# GSM.net
KiCad netlist of a schematic drawn in Altium Designer
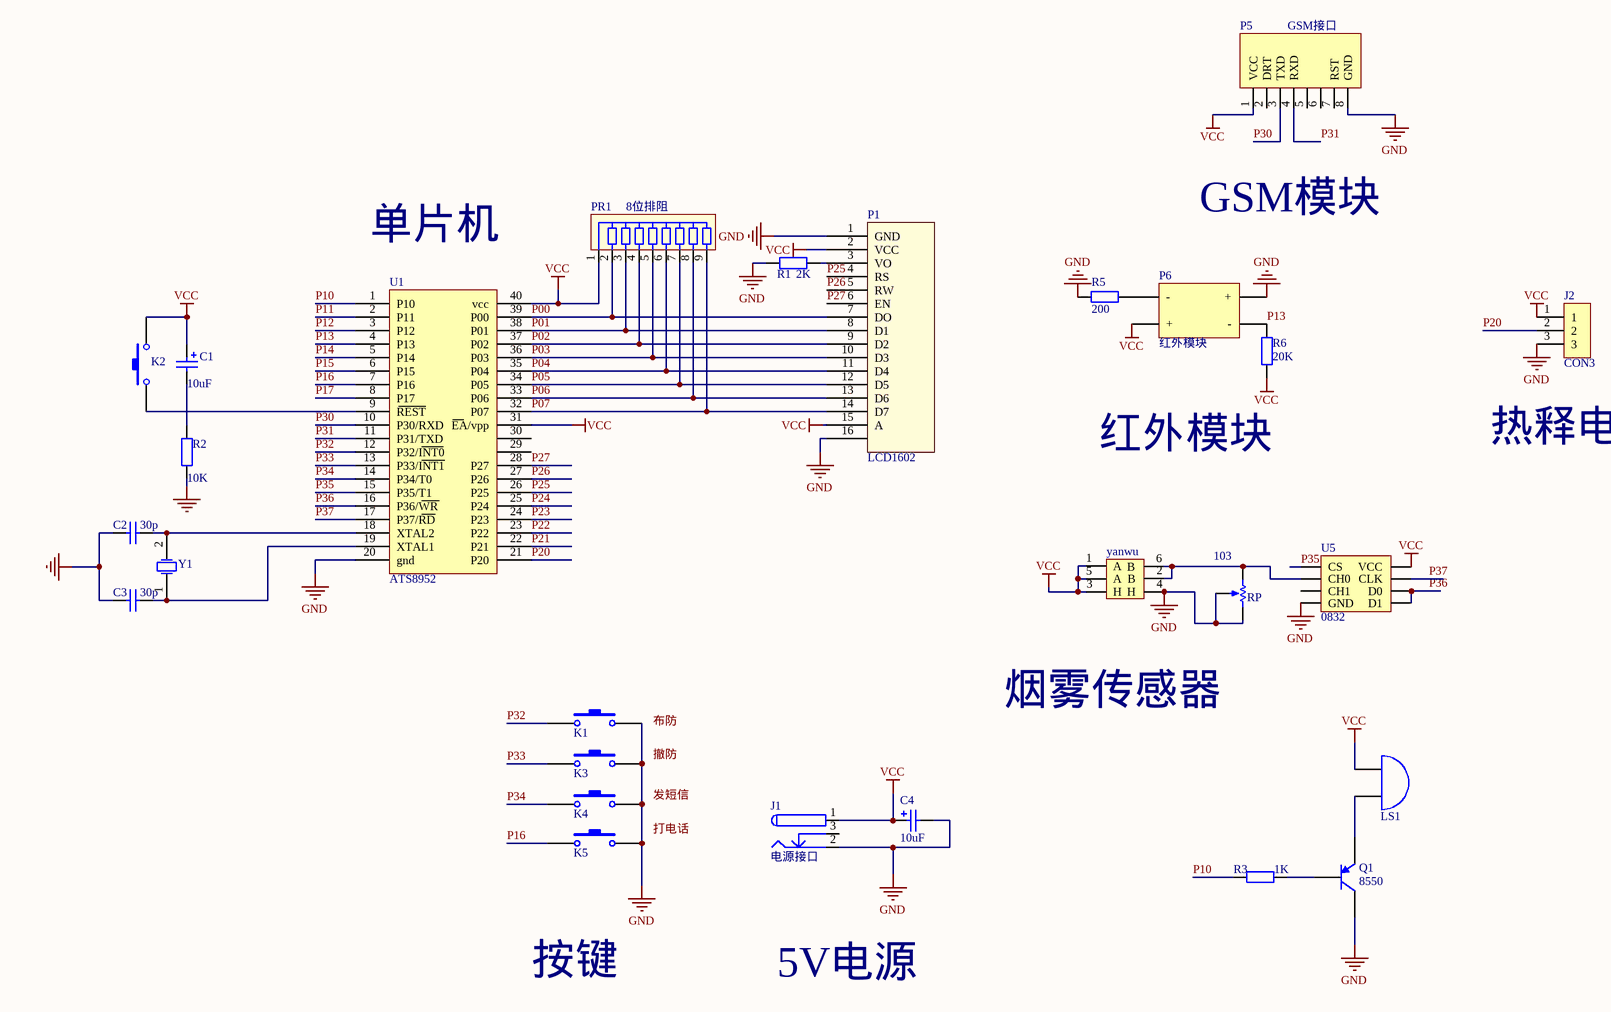
[diagram p0: GSM.SchDoc]

(export (version "E")
  (design (tool "Eeschema 10.0.6"))
  (components
    (comp (ref "C1") (value "10uF") (footprint "CD0.254cm-2") (libsource (lib "YANG") (part "C+")))
    (comp (ref "C2") (value "30p") (footprint "CAP-100") (libsource (lib "YANG") (part "CAP")))
    (comp (ref "C3") (value "30p") (footprint "CAP-100") (libsource (lib "YANG") (part "CAP")))
    (comp (ref "C4") (value "10uF") (footprint "470uF/50V") (libsource (lib "YANG") (part "C+")))
    (comp (ref "J1")
      (value "电源接口")
      (footprint "DC-JACK")
      (description "Low Voltage Power Supply Connector")
      (fields (field (name "PUBLISHER") "Altium Limited"))
      (libsource (lib "Miscellaneous Connectors") (part "PWR2.5"))
    )
    (comp (ref "J2") (value "CON3") (footprint "红外热释电") (libsource (lib "开发板") (part "CON3")))
    (comp (ref "K1") (value "SW-AJ") (footprint "sw-6-6") (libsource (lib "YANG") (part "SW-AJ")))
    (comp (ref "K2") (value "SW-AJ") (footprint "sw-6-6") (libsource (lib "YANG") (part "SW-AJ")))
    (comp (ref "K3") (value "SW-AJ") (footprint "sw-6-6") (libsource (lib "YANG") (part "SW-AJ")))
    (comp (ref "K4") (value "SW-AJ") (footprint "sw-6-6") (libsource (lib "YANG") (part "SW-AJ")))
    (comp (ref "K5") (value "SW-AJ") (footprint "sw-6-6") (libsource (lib "YANG") (part "SW-AJ")))
    (comp (ref "LS1")
      (value "Bell")
      (footprint "Buzzy-Small")
      (description "Electrical Bell")
      (fields (field (name "MANUFACTURER") "Generic Components"))
      (libsource (lib "Miscellaneous Devices") (part "Bell"))
    )
    (comp (ref "P1") (value "LCD1602") (footprint "1602") (libsource (lib "YANG") (part "LCD1602")))
    (comp (ref "P5") (value "GSM接口") (footprint "GSM") (libsource (lib "单片机1") (part "GSM接口")))
    (comp (ref "P6") (value "红外模块") (footprint "红外对管") (libsource (lib "单片机1") (part "红外模块")))
    (comp (ref "PR1") (value "8位排阻") (footprint "HDR1X9") (libsource (lib "YANG") (part "8位排阻")))
    (comp (ref "Q1")
      (value "8550")
      (footprint "TO-92-2N3906")
      (description "PNP General Purpose Amplifier")
      (fields (field (name "PUBLISHER") "Altium Limited"))
      (libsource (lib "Miscellaneous Devices") (part "2N3906"))
    )
    (comp (ref "R1")
      (value "2K")
      (footprint "AXIAL-0.3")
      (description "Resistor")
      (fields (field (name "PUBLISHER") "Altium Limited"))
      (libsource (lib "Miscellaneous Devices") (part "Res2"))
    )
    (comp (ref "R2")
      (value "10K")
      (footprint "AXIAL-0.3")
      (description "Resistor")
      (fields (field (name "PUBLISHER") "Altium Limited"))
      (libsource (lib "") (part "Res2_1"))
    )
    (comp (ref "R3")
      (value "1K")
      (footprint "AXIAL-0.3")
      (description "Resistor")
      (fields (field (name "PUBLISHER") "Altium Limited"))
      (libsource (lib "") (part "Res2_1"))
    )
    (comp (ref "R5")
      (value "200")
      (footprint "AXIAL-0.3")
      (description "Resistor")
      (fields (field (name "PUBLISHER") "Altium Limited"))
      (libsource (lib "") (part "Res2_1"))
    )
    (comp (ref "R6")
      (value "20K")
      (footprint "AXIAL-0.3")
      (description "Resistor")
      (fields (field (name "PUBLISHER") "Altium Limited"))
      (libsource (lib "*") (part "Res2"))
    )
    (comp (ref "RP") (value "103") (footprint "电位器") (libsource (lib "我的库") (part "电位器")))
    (comp (ref "U1") (value "ATS8952") (footprint "DIP40") (libsource (lib "单片机1") (part "ATS8952")))
    (comp (ref "U5") (value "0832") (footprint "DP8") (libsource (lib "我的库") (part "0832")))
    (comp (ref "Y1")
      (value "XTAL")
      (footprint "XTAL-200")
      (description "Crystal Oscillator")
      (fields
        (field (name "MANUFACTURER") "Generic Components")
        (field (name "PUBLISHER") "Altium Hobart Technology Centre")
      )
      (libsource (lib "Miscellaneous Devices") (part "XTAL"))
    )
    (comp (ref "yanwu") (value "烟雾") (footprint "烟雾") (libsource (lib "我的库") (part "烟雾")))
  )
  (nets
    (net (code "1") (name "/P00") (class "Default")
      (node (ref "P1") (pin "7") (pinfunction "DO_7") (pintype "passive"))
      (node (ref "PR1") (pin "2") (pinfunction "2_2") (pintype "passive"))
      (node (ref "U1") (pin "39") (pinfunction "P00_39") (pintype "passive"))
    )
    (net (code "2") (name "/P01") (class "Default")
      (node (ref "P1") (pin "8") (pinfunction "D1_8") (pintype "passive"))
      (node (ref "PR1") (pin "3") (pinfunction "3_3") (pintype "passive"))
      (node (ref "U1") (pin "38") (pinfunction "P01_38") (pintype "passive"))
    )
    (net (code "3") (name "/P02") (class "Default")
      (node (ref "P1") (pin "9") (pinfunction "D2_9") (pintype "passive"))
      (node (ref "PR1") (pin "4") (pinfunction "4_4") (pintype "passive"))
      (node (ref "U1") (pin "37") (pinfunction "P02_37") (pintype "passive"))
    )
    (net (code "4") (name "/P03") (class "Default")
      (node (ref "P1") (pin "10") (pinfunction "D3_10") (pintype "passive"))
      (node (ref "PR1") (pin "5") (pinfunction "5_5") (pintype "passive"))
      (node (ref "U1") (pin "36") (pinfunction "P03_36") (pintype "passive"))
    )
    (net (code "5") (name "/P04") (class "Default")
      (node (ref "P1") (pin "11") (pinfunction "D4_11") (pintype "passive"))
      (node (ref "PR1") (pin "6") (pinfunction "6_6") (pintype "open_collector"))
      (node (ref "U1") (pin "35") (pinfunction "P04_35") (pintype "passive"))
    )
    (net (code "6") (name "/P05") (class "Default")
      (node (ref "P1") (pin "12") (pinfunction "D5_12") (pintype "passive"))
      (node (ref "PR1") (pin "7") (pinfunction "7_7") (pintype "passive"))
      (node (ref "U1") (pin "34") (pinfunction "P05_34") (pintype "passive"))
    )
    (net (code "7") (name "/P06") (class "Default")
      (node (ref "P1") (pin "13") (pinfunction "D6_13") (pintype "passive"))
      (node (ref "PR1") (pin "8") (pinfunction "8_8") (pintype "passive"))
      (node (ref "U1") (pin "33") (pinfunction "P06_33") (pintype "passive"))
    )
    (net (code "8") (name "/P07") (class "Default")
      (node (ref "P1") (pin "14") (pinfunction "D7_14") (pintype "passive"))
      (node (ref "PR1") (pin "9") (pinfunction "9_9") (pintype "passive"))
      (node (ref "U1") (pin "32") (pinfunction "P07_32") (pintype "passive"))
    )
    (net (code "9") (name "/P10") (class "Default")
      (node (ref "R3") (pin "1") (pinfunction "1_1") (pintype "passive"))
      (node (ref "U1") (pin "1") (pinfunction "P10_1") (pintype "passive"))
    )
    (net (code "10") (name "/P11") (class "Default")
      (node (ref "U1") (pin "2") (pinfunction "P11_2") (pintype "passive"))
    )
    (net (code "11") (name "/P12") (class "Default")
      (node (ref "U1") (pin "3") (pinfunction "P12_3") (pintype "passive"))
    )
    (net (code "12") (name "/P13") (class "Default")
      (node (ref "P6") (pin "3") (pinfunction "-_3") (pintype "passive"))
      (node (ref "R6") (pin "2") (pinfunction "2_2") (pintype "passive"))
      (node (ref "U1") (pin "4") (pinfunction "P13_4") (pintype "passive"))
    )
    (net (code "13") (name "/P14") (class "Default")
      (node (ref "U1") (pin "5") (pinfunction "P14_5") (pintype "passive"))
    )
    (net (code "14") (name "/P15") (class "Default")
      (node (ref "U1") (pin "6") (pinfunction "P15_6") (pintype "passive"))
    )
    (net (code "15") (name "/P16") (class "Default")
      (node (ref "K5") (pin "1") (pinfunction "1_1") (pintype "passive"))
      (node (ref "U1") (pin "7") (pinfunction "P16_7") (pintype "passive"))
    )
    (net (code "16") (name "/P17") (class "Default")
      (node (ref "U1") (pin "8") (pinfunction "P17_8") (pintype "passive"))
    )
    (net (code "17") (name "/P20") (class "Default")
      (node (ref "J2") (pin "2") (pinfunction "2_2") (pintype "passive"))
      (node (ref "U1") (pin "21") (pinfunction "P20_21") (pintype "passive"))
    )
    (net (code "18") (name "/P21") (class "Default")
      (node (ref "U1") (pin "22") (pinfunction "P21_22") (pintype "passive"))
    )
    (net (code "19") (name "/P22") (class "Default")
      (node (ref "U1") (pin "23") (pinfunction "P22_23") (pintype "passive"))
    )
    (net (code "20") (name "/P23") (class "Default")
      (node (ref "U1") (pin "24") (pinfunction "P23_24") (pintype "passive"))
    )
    (net (code "21") (name "/P24") (class "Default")
      (node (ref "U1") (pin "25") (pinfunction "P24_25") (pintype "passive"))
    )
    (net (code "22") (name "/P25") (class "Default")
      (node (ref "P1") (pin "4") (pinfunction "RS_4") (pintype "passive"))
      (node (ref "U1") (pin "26") (pinfunction "P25_26") (pintype "passive"))
    )
    (net (code "23") (name "/P26") (class "Default")
      (node (ref "P1") (pin "5") (pinfunction "RW_5") (pintype "passive"))
      (node (ref "U1") (pin "27") (pinfunction "P26_27") (pintype "passive"))
    )
    (net (code "24") (name "/P27") (class "Default")
      (node (ref "P1") (pin "6") (pinfunction "EN_6") (pintype "passive"))
      (node (ref "U1") (pin "28") (pinfunction "P27_28") (pintype "passive"))
    )
    (net (code "25") (name "/P30") (class "Default")
      (node (ref "P5") (pin "3") (pinfunction "TXD_3") (pintype "passive"))
      (node (ref "U1") (pin "10") (pinfunction "P30/RXD_10") (pintype "passive"))
    )
    (net (code "26") (name "/P31") (class "Default")
      (node (ref "P5") (pin "4") (pinfunction "RXD_4") (pintype "passive"))
      (node (ref "U1") (pin "11") (pinfunction "P31/TXD_11") (pintype "passive"))
    )
    (net (code "27") (name "/P32") (class "Default")
      (node (ref "K1") (pin "1") (pinfunction "1_1") (pintype "passive"))
      (node (ref "U1") (pin "12") (pinfunction "P32/INT0_12") (pintype "passive"))
    )
    (net (code "28") (name "/P33") (class "Default")
      (node (ref "K3") (pin "1") (pinfunction "1_1") (pintype "passive"))
      (node (ref "U1") (pin "13") (pinfunction "P33/INT1_13") (pintype "passive"))
    )
    (net (code "29") (name "/P34") (class "Default")
      (node (ref "K4") (pin "1") (pinfunction "1_1") (pintype "passive"))
      (node (ref "U1") (pin "14") (pinfunction "P34/T0_14") (pintype "passive"))
    )
    (net (code "30") (name "/P35") (class "Default")
      (node (ref "U1") (pin "15") (pinfunction "P35/T1_15") (pintype "passive"))
      (node (ref "U5") (pin "1") (pinfunction "CS_1") (pintype "passive"))
    )
    (net (code "31") (name "/P36") (class "Default")
      (node (ref "U1") (pin "16") (pinfunction "P36/WR_16") (pintype "passive"))
      (node (ref "U5") (pin "5") (pinfunction "D1_5") (pintype "passive"))
      (node (ref "U5") (pin "6") (pinfunction "D0_6") (pintype "passive"))
    )
    (net (code "32") (name "/P37") (class "Default")
      (node (ref "U1") (pin "17") (pinfunction "P37/RD_17") (pintype "passive"))
      (node (ref "U5") (pin "7") (pinfunction "CLK_7") (pintype "passive"))
    )
    (net (code "37") (name "GND") (class "Default")
      (node (ref "C2") (pin "1") (pinfunction "1_1") (pintype "passive"))
      (node (ref "C3") (pin "1") (pinfunction "1_1") (pintype "passive"))
      (node (ref "C4") (pin "2") (pinfunction "2_2") (pintype "passive"))
      (node (ref "J1") (pin "2") (pinfunction "2_2") (pintype "power_in"))
      (node (ref "J2") (pin "3") (pinfunction "3_3") (pintype "passive"))
      (node (ref "K1") (pin "2") (pinfunction "2_2") (pintype "passive"))
      (node (ref "K3") (pin "2") (pinfunction "2_2") (pintype "passive"))
      (node (ref "K4") (pin "2") (pinfunction "2_2") (pintype "passive"))
      (node (ref "K5") (pin "2") (pinfunction "2_2") (pintype "passive"))
      (node (ref "P1") (pin "1") (pinfunction "GND_1") (pintype "passive"))
      (node (ref "P1") (pin "16") (pinfunction "K_16") (pintype "passive"))
      (node (ref "P5") (pin "8") (pinfunction "GND_8") (pintype "passive"))
      (node (ref "P6") (pin "4") (pinfunction "+_4") (pintype "passive"))
      (node (ref "Q1") (pin "3") (pinfunction "C_3") (pintype "passive"))
      (node (ref "R1") (pin "1") (pinfunction "1_1") (pintype "passive"))
      (node (ref "R2") (pin "2") (pinfunction "2_2") (pintype "passive"))
      (node (ref "R5") (pin "1") (pinfunction "1_1") (pintype "passive"))
      (node (ref "RP") (pin "2") (pinfunction "TAP_2") (pintype "passive"))
      (node (ref "RP") (pin "3") (pinfunction "BOT_3") (pintype "passive"))
      (node (ref "U1") (pin "20") (pinfunction "gnd_20") (pintype "passive"))
      (node (ref "U5") (pin "4") (pinfunction "GND_4") (pintype "passive"))
      (node (ref "yanwu") (pin "4") (pinfunction "H_4") (pintype "passive"))
    )
    (net (code "38") (name "Net-(C1-Pad2)") (class "Default")
      (node (ref "C1") (pin "2") (pinfunction "2_2") (pintype "passive"))
      (node (ref "R2") (pin "1") (pinfunction "1_1") (pintype "passive"))
    )
    (net (code "39") (name "Net-(LS1-B)") (class "Default")
      (node (ref "LS1") (pin "2") (pinfunction "B_2") (pintype "passive"))
      (node (ref "Q1") (pin "1") (pinfunction "E_1") (pintype "passive"))
    )
    (net (code "40") (name "Net-(P1-VO)") (class "Default")
      (node (ref "P1") (pin "3") (pinfunction "VO_3") (pintype "passive"))
      (node (ref "R1") (pin "2") (pinfunction "2_2") (pintype "passive"))
    )
    (net (code "41") (name "Net-(P6---Pad1)") (class "Default")
      (node (ref "P6") (pin "1") (pinfunction "-_1") (pintype "passive"))
      (node (ref "R5") (pin "2") (pinfunction "2_2") (pintype "passive"))
    )
    (net (code "42") (name "Net-(Q1-B)") (class "Default")
      (node (ref "Q1") (pin "2") (pinfunction "B_2") (pintype "passive"))
      (node (ref "R3") (pin "2") (pinfunction "2_2") (pintype "passive"))
    )
    (net (code "43") (name "Net-(RP-TOP)") (class "Default")
      (node (ref "RP") (pin "1") (pinfunction "TOP_1") (pintype "passive"))
      (node (ref "U5") (pin "2") (pinfunction "CH0_2") (pintype "passive"))
      (node (ref "yanwu") (pin "2") (pinfunction "B_2") (pintype "passive"))
      (node (ref "yanwu") (pin "6") (pinfunction "B_6") (pintype "passive"))
    )
    (net (code "44") (name "Net-(U1-REST)") (class "Default")
      (node (ref "K2") (pin "1") (pinfunction "1_1") (pintype "passive"))
      (node (ref "U1") (pin "9") (pinfunction "REST_9") (pintype "passive"))
    )
    (net (code "45") (name "Net-(U1-XTAL1)") (class "Default")
      (node (ref "C3") (pin "2") (pinfunction "2_2") (pintype "passive"))
      (node (ref "U1") (pin "19") (pinfunction "XTAL1_19") (pintype "passive"))
      (node (ref "Y1") (pin "1") (pinfunction "OSC1_1") (pintype "passive"))
    )
    (net (code "46") (name "Net-(U1-XTAL2)") (class "Default")
      (node (ref "C2") (pin "2") (pinfunction "2_2") (pintype "passive"))
      (node (ref "U1") (pin "18") (pinfunction "XTAL2_18") (pintype "passive"))
      (node (ref "Y1") (pin "2") (pinfunction "OSC2_2") (pintype "passive"))
    )
    (net (code "47") (name "VCC") (class "Default")
      (node (ref "C1") (pin "1") (pinfunction "1_1") (pintype "passive"))
      (node (ref "C4") (pin "1") (pinfunction "1_1") (pintype "passive"))
      (node (ref "J1") (pin "1") (pinfunction "1_1") (pintype "power_in"))
      (node (ref "J2") (pin "1") (pinfunction "1_1") (pintype "passive"))
      (node (ref "K2") (pin "2") (pinfunction "2_2") (pintype "passive"))
      (node (ref "LS1") (pin "1") (pinfunction "A_1") (pintype "passive"))
      (node (ref "P1") (pin "15") (pinfunction "A_15") (pintype "passive"))
      (node (ref "P1") (pin "2") (pinfunction "VCC_2") (pintype "passive"))
      (node (ref "P5") (pin "1") (pinfunction "VCC_1") (pintype "passive"))
      (node (ref "P6") (pin "2") (pinfunction "+_2") (pintype "passive"))
      (node (ref "PR1") (pin "1") (pinfunction "1_1") (pintype "passive"))
      (node (ref "R6") (pin "1") (pinfunction "1_1") (pintype "passive"))
      (node (ref "U1") (pin "31") (pinfunction "EA/vpp_31") (pintype "passive"))
      (node (ref "U1") (pin "40") (pinfunction "vcc_40") (pintype "passive"))
      (node (ref "U5") (pin "8") (pinfunction "VCC_8") (pintype "passive"))
      (node (ref "yanwu") (pin "1") (pinfunction "A_1") (pintype "passive"))
      (node (ref "yanwu") (pin "3") (pinfunction "H_3") (pintype "passive"))
      (node (ref "yanwu") (pin "5") (pinfunction "A_5") (pintype "passive"))
    )
    (net (code "48") (name "unconnected-(J1-Pad3)") (class "Default")
      (node (ref "J1") (pin "3") (pinfunction "3_3") (pintype "power_in"))
    )
    (net (code "49") (name "unconnected-(P5-DRT-Pad2)") (class "Default")
      (node (ref "P5") (pin "2") (pinfunction "DRT_2") (pintype "passive"))
    )
    (net (code "50") (name "unconnected-(P5-Pad5)") (class "Default")
      (node (ref "P5") (pin "5") (pintype "passive"))
    )
    (net (code "51") (name "unconnected-(P5-Pad6)") (class "Default")
      (node (ref "P5") (pin "6") (pintype "passive"))
    )
    (net (code "52") (name "unconnected-(P5-RST-Pad7)") (class "Default")
      (node (ref "P5") (pin "7") (pinfunction "RST_7") (pintype "passive"))
    )
    (net (code "53") (name "unconnected-(U1-Pad29)") (class "Default")
      (node (ref "U1") (pin "29") (pintype "passive"))
    )
    (net (code "54") (name "unconnected-(U1-Pad30)") (class "Default")
      (node (ref "U1") (pin "30") (pintype "passive"))
    )
    (net (code "55") (name "unconnected-(U5-CH1-Pad3)") (class "Default")
      (node (ref "U5") (pin "3") (pinfunction "CH1_3") (pintype "passive"))
    )
  )
)
